# ST_LINK_V2-1.net
KiCad netlist of a schematic drawn in Altium Designer
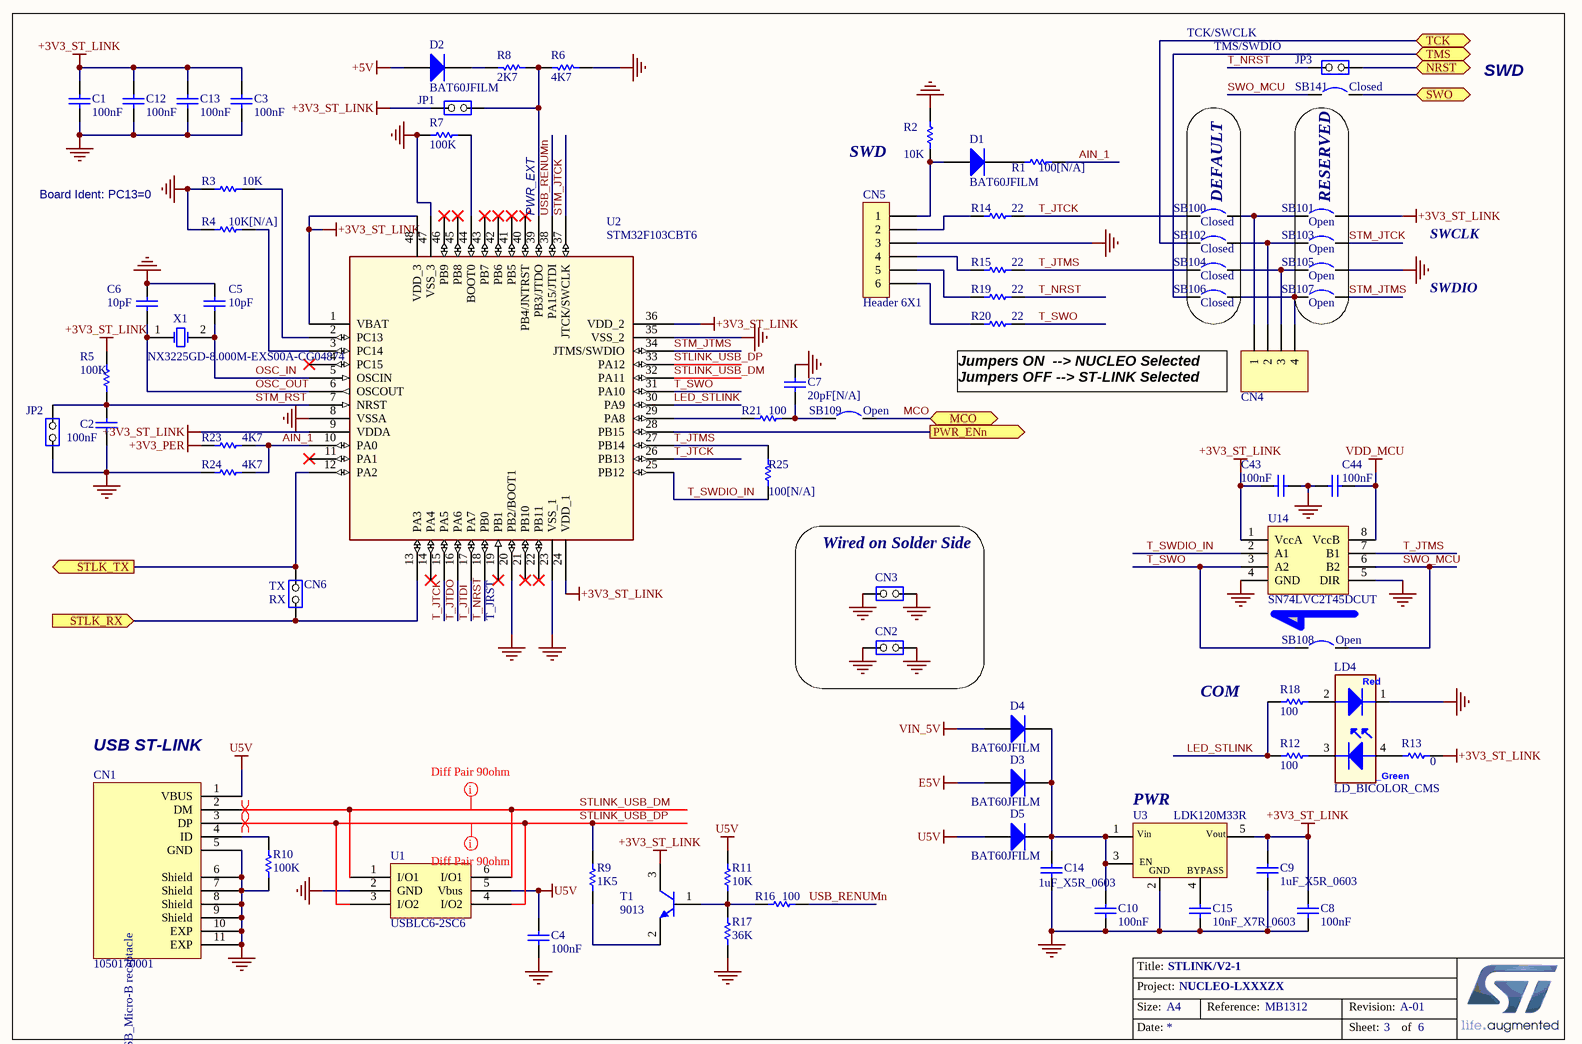
[diagram p0: ST_LINK_V2-1.SCHDOC]

(export (version "E")
  (design (tool "Eeschema 10.0.6"))
  (components
    (comp (ref "C1")
      (value "100nF")
      (footprint "0603C")
      (description "Capacitor 0402 / 0603 / 0805")
      (libsource (lib "MCD_TOOLS") (part "Capacitor_ST"))
    )
    (comp (ref "C2")
      (value "100nF")
      (footprint "0603C")
      (description "Capacitor 0402 / 0603 / 0805")
      (libsource (lib "MCD_TOOLS") (part "Capacitor_ST"))
    )
    (comp (ref "C3")
      (value "100nF")
      (footprint "0603C")
      (description "Capacitor 0402 / 0603 / 0805")
      (libsource (lib "MCD_TOOLS") (part "Capacitor_ST"))
    )
    (comp (ref "C4")
      (value "100nF")
      (footprint "0603C")
      (description "Capacitor 0402 / 0603 / 0805")
      (libsource (lib "MCD_TOOLS") (part "Capacitor_ST"))
    )
    (comp (ref "C5")
      (value "10pF")
      (footprint "0603C")
      (description "Capacitor 0402 / 0603 / 0805")
      (libsource (lib "MCD_TOOLS") (part "Capacitor_ST"))
    )
    (comp (ref "C6")
      (value "10pF")
      (footprint "0603C")
      (description "Capacitor 0402 / 0603 / 0805")
      (libsource (lib "MCD_TOOLS") (part "Capacitor_ST"))
    )
    (comp (ref "C7")
      (value "20pF[N/A]")
      (footprint "0603C")
      (description "Capacitor 0402 / 0603 / 0805")
      (libsource (lib "MCD_TOOLS") (part "Capacitor_ST"))
    )
    (comp (ref "C8")
      (value "100nF")
      (footprint "0603C")
      (description "Capacitor 0402 / 0603 / 0805")
      (libsource (lib "MCD_TOOLS") (part "Capacitor_ST"))
    )
    (comp (ref "C9")
      (value "1uF_X5R_0603")
      (footprint "0603C")
      (description "0603  X5R 1µF")
      (fields (field (name "TOLERANCE") "10%"))
      (libsource (lib "MB963_1") (part "CAP SMD 0603  X5R 1µF 25V 10%"))
    )
    (comp (ref "C10")
      (value "100nF")
      (footprint "0603C")
      (description "Capacitor 0402 / 0603 / 0805")
      (libsource (lib "MCD_TOOLS") (part "Capacitor_ST"))
    )
    (comp (ref "C12")
      (value "100nF")
      (footprint "0603C")
      (description "Capacitor 0402 / 0603 / 0805")
      (libsource (lib "MCD_TOOLS") (part "Capacitor_ST"))
    )
    (comp (ref "C13")
      (value "100nF")
      (footprint "0603C")
      (description "Capacitor 0402 / 0603 / 0805")
      (libsource (lib "MCD_TOOLS") (part "Capacitor_ST"))
    )
    (comp (ref "C14")
      (value "1uF_X5R_0603")
      (footprint "0603C")
      (description "0603  X5R 1µF")
      (fields (field (name "TOLERANCE") "10%"))
      (libsource (lib "MB963_1") (part "CAP SMD 0603  X5R 1µF 25V 10%"))
    )
    (comp (ref "C15")
      (value "10nF_X7R_0603")
      (footprint "0603C")
      (description "0603  X7R 10NF")
      (fields (field (name "TOLERANCE") "10%"))
      (libsource (lib "MB963_1") (part "CAP SMD 0603  X7R 10000PF 50V 10%"))
    )
    (comp (ref "C43")
      (value "100nF")
      (footprint "0603C")
      (description "Capacitor,100nF,10%,16V,X7R,0603,YAGEO")
      (fields (field (name "Comment") "CC0603KRX7R7BB104") (field (name "PUBLISHER") "Altium Limited"))
      (libsource (lib "Miscellaneous Devices") (part "Cap"))
    )
    (comp (ref "C44")
      (value "100nF")
      (footprint "0603C")
      (description "Capacitor,100nF,10%,16V,X7R,0603,YAGEO")
      (fields (field (name "Comment") "CC0603KRX7R7BB104") (field (name "PUBLISHER") "Altium Limited"))
      (libsource (lib "Miscellaneous Devices") (part "Cap"))
    )
    (comp (ref "CN1")
      (value "1050170001")
      (footprint "Molex_1050170001")
      (libsource (lib "Smartphone_accessory") (part "1050170001"))
    )
    (comp (ref "CN2") (value "~") (footprint "HDR_1x2_2R54_V_M") (libsource (lib "*") (part "JP2")))
    (comp (ref "CN3") (value "~") (footprint "HDR_1x2_2R54_V_M") (libsource (lib "*") (part "JP2")))
    (comp (ref "CN4")
      (value "Header 4")
      (footprint "HDR_1x4_2R54_V_M")
      (description "Header, 4-Pin, Single row")
      (fields (field (name "PUBLISHER") "Altium Limited"))
      (libsource (lib "Nucleo_64") (part "Header 4"))
    )
    (comp (ref "CN5")
      (value "Header 6X1")
      (footprint "HDR_1x6_2R54_V_M")
      (description "Header, 6-Pin, Single row")
      (fields (field (name "PUBLISHER") "Altium Limited"))
      (libsource (lib "Nucleo_64") (part "Header 6X1"))
    )
    (comp (ref "CN6") (value "~") (footprint "HDR_1x2_2R54_V_M_S") (libsource (lib "MCD_TOOLS") (part "JP2")))
    (comp (ref "D1")
      (value "BAT60JFILM")
      (footprint "SOD-323")
      (libsource (lib "MB1137") (part "BAT60JFILM"))
    )
    (comp (ref "D2")
      (value "BAT60JFILM")
      (footprint "SOD-323")
      (description "Default Diode")
      (fields (field (name "PUBLISHER") "Altium Limited"))
      (libsource (lib "MB1144_1") (part "Diode"))
    )
    (comp (ref "D3")
      (value "BAT60JFILM")
      (footprint "SOD-323")
      (libsource (lib "MB1137") (part "BAT60JFILM"))
    )
    (comp (ref "D4")
      (value "BAT60JFILM")
      (footprint "SOD-323")
      (libsource (lib "MB1137") (part "BAT60JFILM"))
    )
    (comp (ref "D5")
      (value "BAT60JFILM")
      (footprint "SOD-323")
      (libsource (lib "MB1137") (part "BAT60JFILM"))
    )
    (comp (ref "JP1") (value "~") (footprint "HDR_1x2_2R54_V_M_S") (libsource (lib "*") (part "JP2")))
    (comp (ref "JP2") (value "~") (footprint "HDR_1x2_2R54_V_M_S") (libsource (lib "*") (part "JP2")))
    (comp (ref "JP3") (value "~") (footprint "HDR_1x2_2R54_V_M_S") (libsource (lib "*") (part "JP2")))
    (comp (ref "LD4")
      (value "LD_BICOLOR_CMS")
      (footprint "HSMF-A201")
      (description "Bicolor Led")
      (libsource (lib "MB1137") (part "LD_BICOLOR_CMS"))
    )
    (comp (ref "R1")
      (value "100[N/A]")
      (footprint "0603R")
      (description "Resistor 0402 or 0603 or 0805")
      (libsource (lib "Miscellaneous Devices") (part "Res1"))
    )
    (comp (ref "R2")
      (value "10K")
      (footprint "0603R")
      (description "Resistor 0402 or 0603 or 0805")
      (libsource (lib "Miscellaneous Devices") (part "Res1"))
    )
    (comp (ref "R3")
      (value "10K")
      (footprint "0603R")
      (description "Resistor 0402 or 0603 or 0805")
      (libsource (lib "Miscellaneous Devices") (part "Res1"))
    )
    (comp (ref "R4")
      (value "10K[N/A]")
      (footprint "0603R")
      (description "Resistor 0402 or 0603 or 0805")
      (libsource (lib "Miscellaneous Devices") (part "Res1"))
    )
    (comp (ref "R5")
      (value "100K")
      (footprint "0603R")
      (description "Resistor 0402 or 0603 or 0805")
      (libsource (lib "Miscellaneous Devices") (part "Res1"))
    )
    (comp (ref "R6")
      (value "4K7")
      (footprint "0603R")
      (description "Resistor")
      (fields (field (name "PUBLISHER") "Altium Limited"))
      (libsource (lib "") (part "Res1_2"))
    )
    (comp (ref "R7")
      (value "100K")
      (footprint "0603R")
      (description "Resistor 0402 or 0603 or 0805")
      (libsource (lib "Miscellaneous Devices") (part "Res1"))
    )
    (comp (ref "R8")
      (value "2K7")
      (footprint "0603R")
      (description "Resistor")
      (fields (field (name "PUBLISHER") "Altium Limited"))
      (libsource (lib "") (part "Res1_2"))
    )
    (comp (ref "R9")
      (value "1K5")
      (footprint "0603R")
      (description "Resistor 0402 or 0603 or 0805")
      (libsource (lib "Miscellaneous Devices") (part "Res1"))
    )
    (comp (ref "R10")
      (value "100K")
      (footprint "0603R")
      (description "Resistor 0402 or 0603 or 0805")
      (libsource (lib "Miscellaneous Devices") (part "Res1"))
    )
    (comp (ref "R11")
      (value "10K")
      (footprint "0603R")
      (description "Resistor")
      (fields (field (name "PUBLISHER") "Altium Limited"))
      (libsource (lib "") (part "Res1_1"))
    )
    (comp (ref "R12")
      (value "100")
      (footprint "0603R")
      (description "Resistor 0402 or 0603 or 0805")
      (libsource (lib "Miscellaneous Devices") (part "Res1"))
    )
    (comp (ref "R13")
      (value "0")
      (footprint "0603R")
      (description "Resistor 0402 or 0603 or 0805")
      (libsource (lib "Miscellaneous Devices") (part "Res1"))
    )
    (comp (ref "R14")
      (value "22")
      (footprint "0603R")
      (description "Resistor 0402 or 0603 or 0805")
      (libsource (lib "Miscellaneous Devices") (part "Res1"))
    )
    (comp (ref "R15")
      (value "22")
      (footprint "0603R")
      (description "Resistor 0402 or 0603 or 0805")
      (libsource (lib "Miscellaneous Devices") (part "Res1"))
    )
    (comp (ref "R16")
      (value "100")
      (footprint "0603R")
      (description "Resistor 0402 or 0603 or 0805")
      (libsource (lib "Miscellaneous Devices") (part "Res1"))
    )
    (comp (ref "R17")
      (value "36K")
      (footprint "0603R")
      (description "Resistor")
      (fields (field (name "PUBLISHER") "Altium Limited"))
      (libsource (lib "") (part "Res1_1"))
    )
    (comp (ref "R18")
      (value "100")
      (footprint "0603R")
      (description "Resistor 0402 or 0603 or 0805")
      (libsource (lib "Miscellaneous Devices") (part "Res1"))
    )
    (comp (ref "R19")
      (value "22")
      (footprint "0603R")
      (description "Resistor 0402 or 0603 or 0805")
      (libsource (lib "Miscellaneous Devices") (part "Res1"))
    )
    (comp (ref "R20")
      (value "22")
      (footprint "0603R")
      (description "Resistor 0402 or 0603 or 0805")
      (libsource (lib "Miscellaneous Devices") (part "Res1"))
    )
    (comp (ref "R21")
      (value "100")
      (footprint "0603R")
      (description "Resistor 0402 or 0603 or 0805")
      (libsource (lib "Miscellaneous Devices") (part "Res1"))
    )
    (comp (ref "R23")
      (value "4K7")
      (footprint "0603R")
      (description "Resistor 0402 or 0603 or 0805")
      (libsource (lib "Miscellaneous Devices") (part "Res1"))
    )
    (comp (ref "R24")
      (value "4K7")
      (footprint "0603R")
      (description "Resistor 0402 or 0603 or 0805")
      (libsource (lib "Miscellaneous Devices") (part "Res1"))
    )
    (comp (ref "R25")
      (value "100[N/A]")
      (footprint "0603R")
      (description "Resistor 0402 or 0603 or 0805")
      (libsource (lib "Miscellaneous Devices") (part "Res1"))
    )
    (comp (ref "SB100")
      (value "Closed")
      (footprint "SB_0603")
      (description "Circuit Breaker")
      (fields (field (name "PUBLISHER") "Altium Limited"))
      (libsource (lib "MB1167") (part "Circuit Breaker_close"))
    )
    (comp (ref "SB101")
      (value "Open")
      (footprint "SB_0603")
      (description "Circuit Breaker")
      (fields (field (name "PUBLISHER") "Altium Limited"))
      (libsource (lib "") (part "Circuit Breaker_1"))
    )
    (comp (ref "SB102")
      (value "Closed")
      (footprint "SB_0603")
      (description "Circuit Breaker")
      (fields (field (name "PUBLISHER") "Altium Limited"))
      (libsource (lib "MB1167") (part "Circuit Breaker_close"))
    )
    (comp (ref "SB103")
      (value "Open")
      (footprint "SB_0603")
      (description "Circuit Breaker")
      (fields (field (name "PUBLISHER") "Altium Limited"))
      (libsource (lib "") (part "Circuit Breaker_1"))
    )
    (comp (ref "SB104")
      (value "Closed")
      (footprint "SB_0603")
      (description "Circuit Breaker")
      (fields (field (name "PUBLISHER") "Altium Limited"))
      (libsource (lib "MB1167") (part "Circuit Breaker_close"))
    )
    (comp (ref "SB105")
      (value "Open")
      (footprint "SB_0603")
      (description "Circuit Breaker")
      (fields (field (name "PUBLISHER") "Altium Limited"))
      (libsource (lib "") (part "Circuit Breaker_1"))
    )
    (comp (ref "SB106")
      (value "Closed")
      (footprint "SB_0603")
      (description "Circuit Breaker")
      (fields (field (name "PUBLISHER") "Altium Limited"))
      (libsource (lib "MB1167") (part "Circuit Breaker_close"))
    )
    (comp (ref "SB107")
      (value "Open")
      (footprint "SB_0603")
      (description "Circuit Breaker")
      (fields (field (name "PUBLISHER") "Altium Limited"))
      (libsource (lib "") (part "Circuit Breaker_1"))
    )
    (comp (ref "SB108")
      (value "Open")
      (footprint "SB_0603")
      (description "Circuit Breaker")
      (fields (field (name "PUBLISHER") "Altium Limited"))
      (libsource (lib "MB1167") (part "Circuit Breaker"))
    )
    (comp (ref "SB109")
      (value "Open")
      (footprint "SB_0603")
      (description "Circuit Breaker")
      (fields (field (name "PUBLISHER") "Altium Limited"))
      (libsource (lib "MB1167") (part "Circuit Breaker"))
    )
    (comp (ref "SB141")
      (value "Closed")
      (footprint "SB_0603")
      (description "Circuit Breaker")
      (fields (field (name "PUBLISHER") "Altium Limited"))
      (libsource (lib "MB1167") (part "Circuit Breaker_close"))
    )
    (comp (ref "T1")
      (value "9013")
      (footprint "SOT-23")
      (description "NPN Bipolar Transistor")
      (fields (field (name "PUBLISHER") "Altium Limited"))
      (libsource (lib "MB1167") (part "NPN"))
    )
    (comp (ref "U1")
      (value "USBLC6-2SC6")
      (footprint "SOT23-6L")
      (libsource (lib "MB1137") (part "USBLC6-2SC6"))
    )
    (comp (ref "U2")
      (value "STM32F103CBT6")
      (footprint "LQFP48_0R5_7x7")
      (description "Medium-density performance line ARM-based 32-bit MCU with 64KB Flash")
      (libsource (lib "Nucleo_64") (part "STM32F103CBT6"))
    )
    (comp (ref "U3")
      (value "LDK120M33R")
      (footprint "SOT23-5")
      (description "Ultra low drop-low noise BiCMOS voltage, regulators low ESR capacitors compatible")
      (libsource (lib "MB1246") (part "LDK120M33R"))
    )
    (comp (ref "U14")
      (value "SN74LVC2T45DCUT")
      (footprint "USOP8_0R5_2X3R1")
      (libsource (lib "STLINK") (part "SN74LVC2T45DCUT"))
    )
    (comp (ref "X1")
      (value "NX3225GD-8.000M-EXS00A-CG04874")
      (footprint "OSC_2SM_3R2x2R5")
      (description "Crystal Oscillator")
      (fields (field (name "PUBLISHER") "Altium Limited"))
      (libsource (lib "MB963_1") (part "XTAL"))
    )
  )
  (nets
    (net (code "1") (name "+3V3_PER") (class "Default")
      (node (ref "R23") (pin "1") (pinfunction "1_1") (pintype "passive"))
    )
    (net (code "2") (name "+3V3_ST_LINK") (class "Default")
      (node (ref "C1") (pin "2") (pinfunction "2_2") (pintype "passive"))
      (node (ref "C12") (pin "2") (pinfunction "2_2") (pintype "passive"))
      (node (ref "C13") (pin "2") (pinfunction "2_2") (pintype "passive"))
      (node (ref "C3") (pin "2") (pinfunction "2_2") (pintype "passive"))
      (node (ref "C43") (pin "2") (pinfunction "2_2") (pintype "passive"))
      (node (ref "C8") (pin "2") (pinfunction "2_2") (pintype "passive"))
      (node (ref "C9") (pin "1") (pinfunction "1_1") (pintype "passive"))
      (node (ref "JP1") (pin "1") (pinfunction "COMMON_1") (pintype "passive"))
      (node (ref "R13") (pin "2") (pinfunction "2_2") (pintype "passive"))
      (node (ref "R5") (pin "2") (pinfunction "2_2") (pintype "passive"))
      (node (ref "SB101") (pin "2") (pinfunction "2_2") (pintype "passive"))
      (node (ref "T1") (pin "3") (pinfunction "C_3") (pintype "passive"))
      (node (ref "U14") (pin "1") (pinfunction "VccA_1") (pintype "passive"))
      (node (ref "U2") (pin "1") (pinfunction "VBAT_1") (pintype "power_in"))
      (node (ref "U2") (pin "24") (pinfunction "VDD_1_24") (pintype "power_in"))
      (node (ref "U2") (pin "36") (pinfunction "VDD_2_36") (pintype "power_in"))
      (node (ref "U2") (pin "48") (pinfunction "VDD_3_48") (pintype "power_in"))
      (node (ref "U2") (pin "9") (pinfunction "VDDA_9") (pintype "power_in"))
      (node (ref "U3") (pin "5") (pinfunction "Vout_5") (pintype "passive"))
    )
    (net (code "3") (name "+5V") (class "Default")
      (node (ref "D2") (pin "1") (pinfunction "A_1") (pintype "passive"))
    )
    (net (code "4") (name "/AIN_1") (class "Default")
      (node (ref "R1") (pin "2") (pinfunction "2_2") (pintype "passive"))
      (node (ref "R23") (pin "2") (pinfunction "2_2") (pintype "passive"))
      (node (ref "R24") (pin "2") (pinfunction "2_2") (pintype "passive"))
      (node (ref "U2") (pin "10") (pinfunction "PA0_10") (pintype "bidirectional"))
    )
    (net (code "5") (name "/LED_STLINK") (class "Default")
      (node (ref "R12") (pin "1") (pinfunction "1_1") (pintype "passive"))
      (node (ref "R18") (pin "1") (pinfunction "1_1") (pintype "passive"))
      (node (ref "U2") (pin "30") (pinfunction "PA9_30") (pintype "bidirectional"))
    )
    (net (code "6") (name "/MCO") (class "Default")
      (node (ref "SB109") (pin "1") (pinfunction "1_1") (pintype "passive"))
    )
    (net (code "7") (name "/NRST") (class "Default")
      (node (ref "JP3") (pin "2") (pinfunction "NO_2") (pintype "passive"))
    )
    (net (code "8") (name "/OSC_IN") (class "Default")
      (node (ref "C5") (pin "1") (pinfunction "1_1") (pintype "passive"))
      (node (ref "U2") (pin "5") (pinfunction "OSCIN_5") (pintype "input"))
      (node (ref "X1") (pin "2") (pinfunction "OSC2_2") (pintype "passive"))
    )
    (net (code "9") (name "/OSC_OUT") (class "Default")
      (node (ref "C6") (pin "1") (pinfunction "1_1") (pintype "passive"))
      (node (ref "U2") (pin "6") (pinfunction "OSCOUT_6") (pintype "output"))
      (node (ref "X1") (pin "1") (pinfunction "OSC1_1") (pintype "passive"))
    )
    (net (code "10") (name "/PWR_ENn") (class "Default")
      (node (ref "U2") (pin "28") (pinfunction "PB15_28") (pintype "bidirectional"))
    )
    (net (code "11") (name "/STLINK_USB_DM") (class "Default")
      (node (ref "CN1") (pin "2") (pinfunction "DM_2") (pintype "passive"))
      (node (ref "U1") (pin "1") (pinfunction "I/O1_1") (pintype "passive"))
      (node (ref "U1") (pin "6") (pinfunction "I/O1_6") (pintype "passive"))
      (node (ref "U2") (pin "32") (pinfunction "PA11_32") (pintype "bidirectional"))
    )
    (net (code "12") (name "/STLINK_USB_DP") (class "Default")
      (node (ref "CN1") (pin "3") (pinfunction "DP_3") (pintype "passive"))
      (node (ref "R9") (pin "1") (pinfunction "1_1") (pintype "passive"))
      (node (ref "U1") (pin "3") (pinfunction "I/O2_3") (pintype "passive"))
      (node (ref "U1") (pin "4") (pinfunction "I/O2_4") (pintype "passive"))
      (node (ref "U2") (pin "33") (pinfunction "PA12_33") (pintype "bidirectional"))
    )
    (net (code "13") (name "/STLK_RX") (class "Default")
      (node (ref "CN6") (pin "1") (pinfunction "COMMON_1") (pintype "passive"))
      (node (ref "U2") (pin "13") (pinfunction "PA3_13") (pintype "bidirectional"))
    )
    (net (code "14") (name "/STLK_TX") (class "Default")
      (node (ref "CN6") (pin "2") (pinfunction "NO_2") (pintype "passive"))
      (node (ref "U2") (pin "12") (pinfunction "PA2_12") (pintype "bidirectional"))
    )
    (net (code "15") (name "/STM_JTCK") (class "Default")
      (node (ref "SB103") (pin "2") (pinfunction "2_2") (pintype "passive"))
      (node (ref "U2") (pin "37") (pinfunction "JTCK/SWCLK_37") (pintype "bidirectional"))
    )
    (net (code "16") (name "/STM_JTMS") (class "Default")
      (node (ref "SB107") (pin "2") (pinfunction "2_2") (pintype "passive"))
      (node (ref "U2") (pin "34") (pinfunction "JTMS/SWDIO_34") (pintype "bidirectional"))
    )
    (net (code "17") (name "/STM_RST") (class "Default")
      (node (ref "C2") (pin "2") (pinfunction "2_2") (pintype "passive"))
      (node (ref "JP2") (pin "2") (pinfunction "NO_2") (pintype "passive"))
      (node (ref "R5") (pin "1") (pinfunction "1_1") (pintype "passive"))
      (node (ref "U2") (pin "7") (pinfunction "NRST_7") (pintype "input"))
    )
    (net (code "18") (name "/SWO") (class "Default")
      (node (ref "SB141") (pin "2") (pinfunction "2_2") (pintype "passive"))
    )
    (net (code "19") (name "/SWO_MCU") (class "Default")
      (node (ref "SB108") (pin "1") (pinfunction "1_1") (pintype "passive"))
      (node (ref "SB141") (pin "1") (pinfunction "1_1") (pintype "passive"))
      (node (ref "U14") (pin "6") (pinfunction "B2_6") (pintype "passive"))
    )
    (net (code "20") (name "/TCK") (class "Default")
      (node (ref "SB102") (pin "1") (pinfunction "1_1") (pintype "passive"))
    )
    (net (code "21") (name "/TMS") (class "Default")
      (node (ref "SB106") (pin "1") (pinfunction "1_1") (pintype "passive"))
    )
    (net (code "22") (name "/T_JTCK") (class "Default")
      (node (ref "R14") (pin "2") (pinfunction "2_2") (pintype "passive"))
      (node (ref "SB100") (pin "1") (pinfunction "1_1") (pintype "passive"))
      (node (ref "U2") (pin "15") (pinfunction "PA5_15") (pintype "bidirectional"))
      (node (ref "U2") (pin "26") (pinfunction "PB13_26") (pintype "bidirectional"))
    )
    (net (code "23") (name "/T_JTDI") (class "Default")
      (node (ref "U2") (pin "17") (pinfunction "PA7_17") (pintype "bidirectional"))
    )
    (net (code "24") (name "/T_JTDO") (class "Default")
      (node (ref "U2") (pin "16") (pinfunction "PA6_16") (pintype "bidirectional"))
    )
    (net (code "25") (name "/T_JTMS") (class "Default")
      (node (ref "R15") (pin "2") (pinfunction "2_2") (pintype "passive"))
      (node (ref "R25") (pin "2") (pinfunction "2_2") (pintype "passive"))
      (node (ref "SB104") (pin "1") (pinfunction "1_1") (pintype "passive"))
      (node (ref "U14") (pin "7") (pinfunction "B1_7") (pintype "passive"))
      (node (ref "U2") (pin "27") (pinfunction "PB14_27") (pintype "bidirectional"))
    )
    (net (code "26") (name "/T_NRST") (class "Default")
      (node (ref "JP3") (pin "1") (pinfunction "COMMON_1") (pintype "passive"))
      (node (ref "R19") (pin "2") (pinfunction "2_2") (pintype "passive"))
      (node (ref "U2") (pin "18") (pinfunction "PB0_18") (pintype "bidirectional"))
    )
    (net (code "27") (name "/T_SWDIO_IN") (class "Default")
      (node (ref "R25") (pin "1") (pinfunction "1_1") (pintype "passive"))
      (node (ref "U14") (pin "2") (pinfunction "A1_2") (pintype "passive"))
      (node (ref "U2") (pin "25") (pinfunction "PB12_25") (pintype "bidirectional"))
    )
    (net (code "28") (name "/T_SWO") (class "Default")
      (node (ref "R20") (pin "2") (pinfunction "2_2") (pintype "passive"))
      (node (ref "SB108") (pin "2") (pinfunction "2_2") (pintype "passive"))
      (node (ref "U14") (pin "3") (pinfunction "A2_3") (pintype "passive"))
      (node (ref "U2") (pin "31") (pinfunction "PA10_31") (pintype "bidirectional"))
    )
    (net (code "29") (name "/USB_RENUMn") (class "Default")
      (node (ref "R16") (pin "2") (pinfunction "2_2") (pintype "passive"))
      (node (ref "U2") (pin "38") (pinfunction "PA15/JTDI_38") (pintype "bidirectional"))
    )
    (net (code "30") (name "E5V") (class "Default")
      (node (ref "D3") (pin "1") (pinfunction "A_1") (pintype "passive"))
    )
    (net (code "31") (name "GND") (class "Default")
      (node (ref "C1") (pin "1") (pinfunction "1_1") (pintype "passive"))
      (node (ref "C10") (pin "1") (pinfunction "1_1") (pintype "passive"))
      (node (ref "C12") (pin "1") (pinfunction "1_1") (pintype "passive"))
      (node (ref "C13") (pin "1") (pinfunction "1_1") (pintype "passive"))
      (node (ref "C14") (pin "1") (pinfunction "1_1") (pintype "passive"))
      (node (ref "C15") (pin "1") (pinfunction "1_1") (pintype "passive"))
      (node (ref "C2") (pin "1") (pinfunction "1_1") (pintype "passive"))
      (node (ref "C3") (pin "1") (pinfunction "1_1") (pintype "passive"))
      (node (ref "C4") (pin "1") (pinfunction "1_1") (pintype "passive"))
      (node (ref "C43") (pin "1") (pinfunction "1_1") (pintype "passive"))
      (node (ref "C44") (pin "2") (pinfunction "2_2") (pintype "passive"))
      (node (ref "C5") (pin "2") (pinfunction "2_2") (pintype "passive"))
      (node (ref "C6") (pin "2") (pinfunction "2_2") (pintype "passive"))
      (node (ref "C7") (pin "2") (pinfunction "2_2") (pintype "passive"))
      (node (ref "C8") (pin "1") (pinfunction "1_1") (pintype "passive"))
      (node (ref "C9") (pin "2") (pinfunction "2_2") (pintype "passive"))
      (node (ref "CN1") (pin "10") (pinfunction "EXP_10") (pintype "passive"))
      (node (ref "CN1") (pin "11") (pinfunction "EXP_11") (pintype "passive"))
      (node (ref "CN1") (pin "5") (pinfunction "GND_5") (pintype "passive"))
      (node (ref "CN1") (pin "6") (pinfunction "Shield_6") (pintype "passive"))
      (node (ref "CN1") (pin "7") (pinfunction "Shield_7") (pintype "passive"))
      (node (ref "CN1") (pin "8") (pinfunction "Shield_8") (pintype "passive"))
      (node (ref "CN1") (pin "9") (pinfunction "Shield_9") (pintype "passive"))
      (node (ref "CN2") (pin "1") (pinfunction "COMMON_1") (pintype "passive"))
      (node (ref "CN2") (pin "2") (pinfunction "NO_2") (pintype "passive"))
      (node (ref "CN3") (pin "1") (pinfunction "COMMON_1") (pintype "passive"))
      (node (ref "CN3") (pin "2") (pinfunction "NO_2") (pintype "passive"))
      (node (ref "CN5") (pin "3") (pinfunction "3_3") (pintype "passive"))
      (node (ref "JP2") (pin "1") (pinfunction "COMMON_1") (pintype "passive"))
      (node (ref "LD4") (pin "1") (pinfunction "1_1") (pintype "passive"))
      (node (ref "R10") (pin "2") (pinfunction "2_2") (pintype "passive"))
      (node (ref "R17") (pin "1") (pinfunction "1_1") (pintype "passive"))
      (node (ref "R2") (pin "2") (pinfunction "2_2") (pintype "passive"))
      (node (ref "R24") (pin "1") (pinfunction "1_1") (pintype "passive"))
      (node (ref "R3") (pin "1") (pinfunction "1_1") (pintype "passive"))
      (node (ref "R4") (pin "1") (pinfunction "1_1") (pintype "passive"))
      (node (ref "R6") (pin "2") (pinfunction "2_2") (pintype "passive"))
      (node (ref "R7") (pin "1") (pinfunction "1_1") (pintype "passive"))
      (node (ref "SB105") (pin "2") (pinfunction "2_2") (pintype "passive"))
      (node (ref "U1") (pin "2") (pinfunction "GND_2") (pintype "passive"))
      (node (ref "U14") (pin "4") (pinfunction "GND_4") (pintype "passive"))
      (node (ref "U14") (pin "5") (pinfunction "DIR_5") (pintype "passive"))
      (node (ref "U2") (pin "20") (pinfunction "PB2/BOOT1_20") (pintype "bidirectional"))
      (node (ref "U2") (pin "23") (pinfunction "VSS_1_23") (pintype "power_in"))
      (node (ref "U2") (pin "35") (pinfunction "VSS_2_35") (pintype "power_in"))
      (node (ref "U2") (pin "47") (pinfunction "VSS_3_47") (pintype "power_in"))
      (node (ref "U2") (pin "8") (pinfunction "VSSA_8") (pintype "power_in"))
      (node (ref "U3") (pin "2") (pinfunction "GND_2") (pintype "passive"))
    )
    (net (code "32") (name "Net-(C7-Pad1)") (class "Default")
      (node (ref "C7") (pin "1") (pinfunction "1_1") (pintype "passive"))
      (node (ref "R21") (pin "2") (pinfunction "2_2") (pintype "passive"))
      (node (ref "SB109") (pin "2") (pinfunction "2_2") (pintype "passive"))
    )
    (net (code "33") (name "Net-(CN1-ID)") (class "Default")
      (node (ref "CN1") (pin "4") (pinfunction "ID_4") (pintype "passive"))
      (node (ref "R10") (pin "1") (pinfunction "1_1") (pintype "passive"))
    )
    (net (code "34") (name "Net-(CN4-Pad1)") (class "Default")
      (node (ref "CN4") (pin "1") (pinfunction "1_1") (pintype "passive"))
      (node (ref "SB100") (pin "2") (pinfunction "2_2") (pintype "passive"))
      (node (ref "SB101") (pin "1") (pinfunction "1_1") (pintype "passive"))
    )
    (net (code "35") (name "Net-(CN4-Pad2)") (class "Default")
      (node (ref "CN4") (pin "2") (pinfunction "2_2") (pintype "passive"))
      (node (ref "SB102") (pin "2") (pinfunction "2_2") (pintype "passive"))
      (node (ref "SB103") (pin "1") (pinfunction "1_1") (pintype "passive"))
    )
    (net (code "36") (name "Net-(CN4-Pad3)") (class "Default")
      (node (ref "CN4") (pin "3") (pinfunction "3_3") (pintype "passive"))
      (node (ref "SB104") (pin "2") (pinfunction "2_2") (pintype "passive"))
      (node (ref "SB105") (pin "1") (pinfunction "1_1") (pintype "passive"))
    )
    (net (code "37") (name "Net-(CN4-Pad4)") (class "Default")
      (node (ref "CN4") (pin "4") (pinfunction "4_4") (pintype "passive"))
      (node (ref "SB106") (pin "2") (pinfunction "2_2") (pintype "passive"))
      (node (ref "SB107") (pin "1") (pinfunction "1_1") (pintype "passive"))
    )
    (net (code "38") (name "Net-(CN5-Pad2)") (class "Default")
      (node (ref "CN5") (pin "2") (pinfunction "2_2") (pintype "passive"))
      (node (ref "R14") (pin "1") (pinfunction "1_1") (pintype "passive"))
    )
    (net (code "39") (name "Net-(CN5-Pad4)") (class "Default")
      (node (ref "CN5") (pin "4") (pinfunction "4_4") (pintype "passive"))
      (node (ref "R15") (pin "1") (pinfunction "1_1") (pintype "passive"))
    )
    (net (code "40") (name "Net-(CN5-Pad5)") (class "Default")
      (node (ref "CN5") (pin "5") (pinfunction "5_5") (pintype "passive"))
      (node (ref "R19") (pin "1") (pinfunction "1_1") (pintype "passive"))
    )
    (net (code "41") (name "Net-(CN5-Pad6)") (class "Default")
      (node (ref "CN5") (pin "6") (pinfunction "6_6") (pintype "passive"))
      (node (ref "R20") (pin "1") (pinfunction "1_1") (pintype "passive"))
    )
    (net (code "42") (name "Net-(D1-A)") (class "Default")
      (node (ref "CN5") (pin "1") (pinfunction "1_1") (pintype "passive"))
      (node (ref "D1") (pin "1") (pinfunction "A_1") (pintype "passive"))
      (node (ref "R2") (pin "1") (pinfunction "1_1") (pintype "passive"))
    )
    (net (code "43") (name "Net-(D1-K)") (class "Default")
      (node (ref "D1") (pin "2") (pinfunction "K_2") (pintype "passive"))
      (node (ref "R1") (pin "1") (pinfunction "1_1") (pintype "passive"))
    )
    (net (code "44") (name "Net-(D2-K)") (class "Default")
      (node (ref "D2") (pin "2") (pinfunction "K_2") (pintype "passive"))
      (node (ref "R8") (pin "1") (pinfunction "1_1") (pintype "passive"))
    )
    (net (code "45") (name "Net-(D3-K)") (class "Default")
      (node (ref "C10") (pin "2") (pinfunction "2_2") (pintype "passive"))
      (node (ref "C14") (pin "2") (pinfunction "2_2") (pintype "passive"))
      (node (ref "D3") (pin "2") (pinfunction "K_2") (pintype "passive"))
      (node (ref "D4") (pin "2") (pinfunction "K_2") (pintype "passive"))
      (node (ref "D5") (pin "2") (pinfunction "K_2") (pintype "passive"))
      (node (ref "U3") (pin "1") (pinfunction "Vin_1") (pintype "passive"))
      (node (ref "U3") (pin "3") (pinfunction "CE_3") (pintype "passive"))
    )
    (net (code "46") (name "Net-(JP1-NO)") (class "Default")
      (node (ref "JP1") (pin "2") (pinfunction "NO_2") (pintype "passive"))
      (node (ref "R6") (pin "1") (pinfunction "1_1") (pintype "passive"))
      (node (ref "R8") (pin "2") (pinfunction "2_2") (pintype "passive"))
      (node (ref "U2") (pin "39") (pinfunction "PB3/JTDO_39") (pintype "bidirectional"))
    )
    (net (code "47") (name "Net-(LD4-Pad2)") (class "Default")
      (node (ref "LD4") (pin "2") (pinfunction "2_2") (pintype "passive"))
      (node (ref "R18") (pin "2") (pinfunction "2_2") (pintype "passive"))
    )
    (net (code "48") (name "Net-(LD4-Pad3)") (class "Default")
      (node (ref "LD4") (pin "3") (pinfunction "3_3") (pintype "passive"))
      (node (ref "R12") (pin "2") (pinfunction "2_2") (pintype "passive"))
    )
    (net (code "49") (name "Net-(LD4-Pad4)") (class "Default")
      (node (ref "LD4") (pin "4") (pinfunction "4_4") (pintype "passive"))
      (node (ref "R13") (pin "1") (pinfunction "1_1") (pintype "passive"))
    )
    (net (code "50") (name "Net-(T1-B)") (class "Default")
      (node (ref "R11") (pin "1") (pinfunction "1_1") (pintype "passive"))
      (node (ref "R16") (pin "1") (pinfunction "1_1") (pintype "passive"))
      (node (ref "R17") (pin "2") (pinfunction "2_2") (pintype "passive"))
      (node (ref "T1") (pin "1") (pinfunction "B_1") (pintype "passive"))
    )
    (net (code "51") (name "Net-(T1-E)") (class "Default")
      (node (ref "R9") (pin "2") (pinfunction "2_2") (pintype "passive"))
      (node (ref "T1") (pin "2") (pinfunction "E_2") (pintype "passive"))
    )
    (net (code "52") (name "Net-(U2-BOOT0)") (class "Default")
      (node (ref "R7") (pin "2") (pinfunction "2_2") (pintype "passive"))
      (node (ref "U2") (pin "44") (pinfunction "BOOT0_44") (pintype "bidirectional"))
    )
    (net (code "53") (name "Net-(U2-PA8)") (class "Default")
      (node (ref "R21") (pin "1") (pinfunction "1_1") (pintype "passive"))
      (node (ref "U2") (pin "29") (pinfunction "PA8_29") (pintype "bidirectional"))
    )
    (net (code "54") (name "Net-(U2-PC13)") (class "Default")
      (node (ref "R3") (pin "2") (pinfunction "2_2") (pintype "passive"))
      (node (ref "U2") (pin "2") (pinfunction "PC13_2") (pintype "bidirectional"))
    )
    (net (code "55") (name "Net-(U2-PC14)") (class "Default")
      (node (ref "R4") (pin "2") (pinfunction "2_2") (pintype "passive"))
      (node (ref "U2") (pin "3") (pinfunction "PC14_3") (pintype "bidirectional"))
    )
    (net (code "56") (name "Net-(U3-BYPASS)") (class "Default")
      (node (ref "C15") (pin "2") (pinfunction "2_2") (pintype "passive"))
      (node (ref "U3") (pin "4") (pinfunction "BYPASS_4") (pintype "passive"))
    )
    (net (code "57") (name "U5V") (class "Default")
      (node (ref "C4") (pin "2") (pinfunction "2_2") (pintype "passive"))
      (node (ref "CN1") (pin "1") (pinfunction "VBUS_1") (pintype "passive"))
      (node (ref "D5") (pin "1") (pinfunction "A_1") (pintype "passive"))
      (node (ref "R11") (pin "2") (pinfunction "2_2") (pintype "passive"))
      (node (ref "U1") (pin "5") (pinfunction "Vbus_5") (pintype "passive"))
    )
    (net (code "58") (name "VDD_MCU") (class "Default")
      (node (ref "C44") (pin "1") (pinfunction "1_1") (pintype "passive"))
      (node (ref "U14") (pin "8") (pinfunction "VccB_8") (pintype "passive"))
    )
    (net (code "59") (name "VIN_5V") (class "Default")
      (node (ref "D4") (pin "1") (pinfunction "A_1") (pintype "passive"))
    )
    (net (code "60") (name "unconnected-(U2-PA1-Pad11)") (class "Default")
      (node (ref "U2") (pin "11") (pinfunction "PA1_11") (pintype "bidirectional+no_connect"))
    )
    (net (code "61") (name "unconnected-(U2-PA4-Pad14)") (class "Default")
      (node (ref "U2") (pin "14") (pinfunction "PA4_14") (pintype "bidirectional+no_connect"))
    )
    (net (code "62") (name "unconnected-(U2-PB1-Pad19)") (class "Default")
      (node (ref "U2") (pin "19") (pinfunction "PB1_19") (pintype "input+no_connect"))
    )
    (net (code "63") (name "unconnected-(U2-PB4{slash}JNTRST-Pad40)") (class "Default")
      (node (ref "U2") (pin "40") (pinfunction "PB4/JNTRST_40") (pintype "bidirectional+no_connect"))
    )
    (net (code "64") (name "unconnected-(U2-PB5-Pad41)") (class "Default")
      (node (ref "U2") (pin "41") (pinfunction "PB5_41") (pintype "bidirectional+no_connect"))
    )
    (net (code "65") (name "unconnected-(U2-PB6-Pad42)") (class "Default")
      (node (ref "U2") (pin "42") (pinfunction "PB6_42") (pintype "bidirectional+no_connect"))
    )
    (net (code "66") (name "unconnected-(U2-PB7-Pad43)") (class "Default")
      (node (ref "U2") (pin "43") (pinfunction "PB7_43") (pintype "bidirectional+no_connect"))
    )
    (net (code "67") (name "unconnected-(U2-PB8-Pad45)") (class "Default")
      (node (ref "U2") (pin "45") (pinfunction "PB8_45") (pintype "bidirectional+no_connect"))
    )
    (net (code "68") (name "unconnected-(U2-PB9-Pad46)") (class "Default")
      (node (ref "U2") (pin "46") (pinfunction "PB9_46") (pintype "bidirectional+no_connect"))
    )
    (net (code "69") (name "unconnected-(U2-PB10-Pad21)") (class "Default")
      (node (ref "U2") (pin "21") (pinfunction "PB10_21") (pintype "bidirectional+no_connect"))
    )
    (net (code "70") (name "unconnected-(U2-PB11-Pad22)") (class "Default")
      (node (ref "U2") (pin "22") (pinfunction "PB11_22") (pintype "bidirectional+no_connect"))
    )
    (net (code "71") (name "unconnected-(U2-PC15-Pad4)") (class "Default")
      (node (ref "U2") (pin "4") (pinfunction "PC15_4") (pintype "bidirectional+no_connect"))
    )
  )
)
